# RCJ_OnStage2024_FC_mcu.net
KiCad netlist of a schematic drawn in Altium Designer
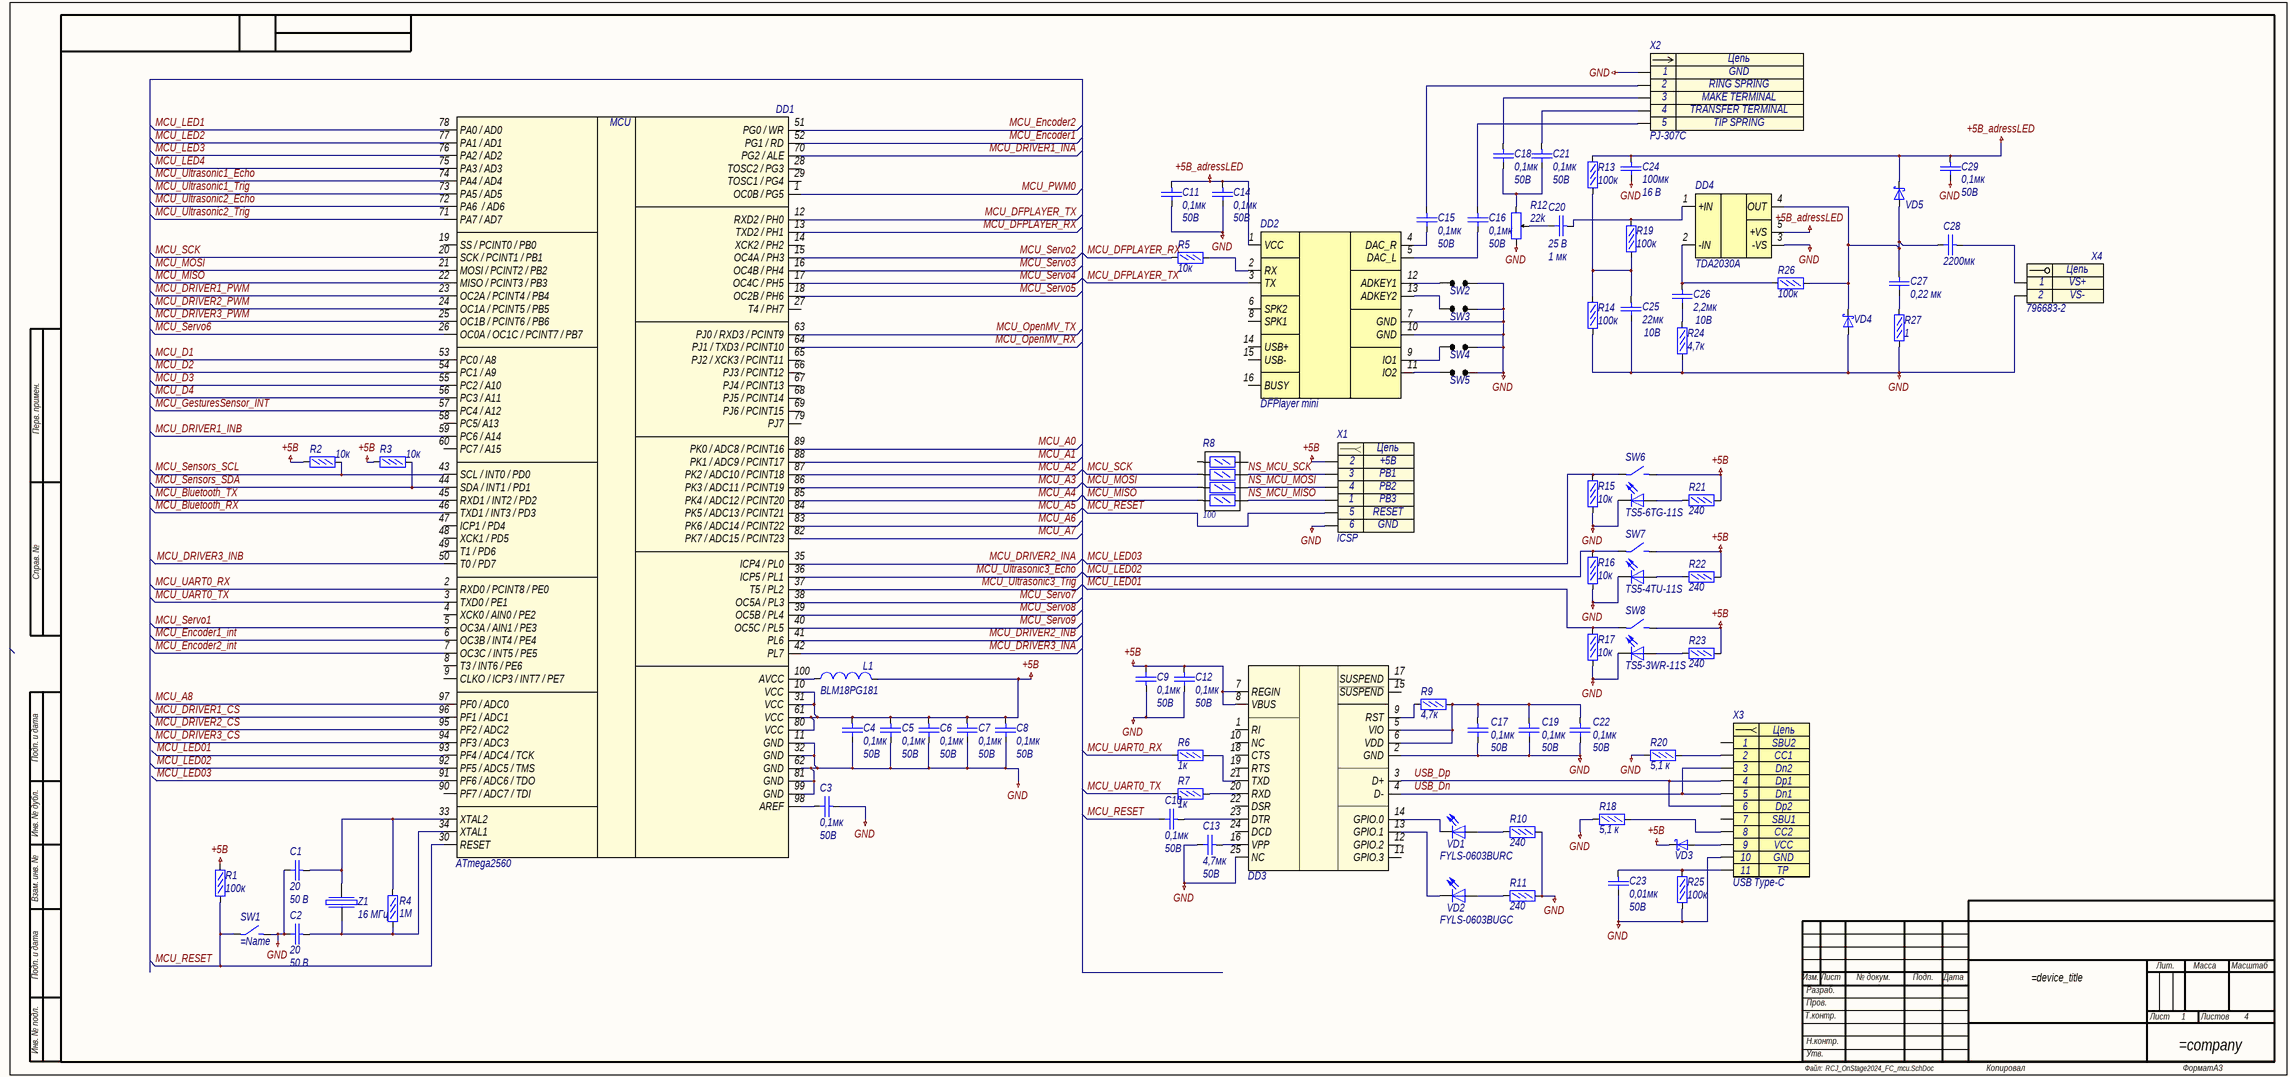
[diagram p0: RCJ_OnStage2024_FC_mcu.SchDoc]

(export (version "E")
  (design (tool "Eeschema 10.0.6"))
  (components
    (comp (ref "C1")
      (value "20")
      (footprint "C0603")
      (description "Конденсатор керамический 20пФ 50В")
      (fields (field (name "VOLTAGE") "50 В"))
      (libsource (lib "capacitors") (part "CC0603JRNPO9BN200"))
    )
    (comp (ref "C2")
      (value "20")
      (footprint "C0603")
      (description "Конденсатор керамический 20пФ 50В")
      (fields (field (name "VOLTAGE") "50 В"))
      (libsource (lib "capacitors") (part "CC0603JRNPO9BN200"))
    )
    (comp (ref "C3")
      (value "0,1мк")
      (footprint "C0603")
      (description "Конденсатор кер. 0,1мкФ 50В X7R")
      (fields (field (name "MANUFACTURER") "Murata") (field (name "VOLTAGE") "50В"))
      (libsource (lib "capacitors") (part "GRM188R71H104KA93D"))
    )
    (comp (ref "C4")
      (value "0,1мк")
      (footprint "C0603")
      (description "Конденсатор кер. 0,1мкФ 50В X7R")
      (fields (field (name "MANUFACTURER") "Murata") (field (name "VOLTAGE") "50В"))
      (libsource (lib "capacitors") (part "GRM188R71H104KA93D"))
    )
    (comp (ref "C5")
      (value "0,1мк")
      (footprint "C0603")
      (description "Конденсатор кер. 0,1мкФ 50В X7R")
      (fields (field (name "MANUFACTURER") "Murata") (field (name "VOLTAGE") "50В"))
      (libsource (lib "capacitors") (part "GRM188R71H104KA93D"))
    )
    (comp (ref "C6")
      (value "0,1мк")
      (footprint "C0603")
      (description "Конденсатор кер. 0,1мкФ 50В X7R")
      (fields (field (name "MANUFACTURER") "Murata") (field (name "VOLTAGE") "50В"))
      (libsource (lib "capacitors") (part "GRM188R71H104KA93D"))
    )
    (comp (ref "C7")
      (value "0,1мк")
      (footprint "C0603")
      (description "Конденсатор кер. 0,1мкФ 50В X7R")
      (fields (field (name "MANUFACTURER") "Murata") (field (name "VOLTAGE") "50В"))
      (libsource (lib "capacitors") (part "GRM188R71H104KA93D"))
    )
    (comp (ref "C8")
      (value "0,1мк")
      (footprint "C0603")
      (description "Конденсатор кер. 0,1мкФ 50В X7R")
      (fields (field (name "MANUFACTURER") "Murata") (field (name "VOLTAGE") "50В"))
      (libsource (lib "capacitors") (part "GRM188R71H104KA93D"))
    )
    (comp (ref "C9")
      (value "0,1мк")
      (footprint "C0603")
      (description "Конденсатор кер. 0,1мкФ 50В X7R")
      (fields (field (name "MANUFACTURER") "Murata") (field (name "VOLTAGE") "50В"))
      (libsource (lib "capacitors") (part "GRM188R71H104KA93D"))
    )
    (comp (ref "C10")
      (value "0,1мк")
      (footprint "C0603")
      (description "Конденсатор кер. 0,1мкФ 50В X7R")
      (fields (field (name "MANUFACTURER") "Murata") (field (name "VOLTAGE") "50В"))
      (libsource (lib "capacitors") (part "GRM188R71H104KA93D"))
    )
    (comp (ref "C11")
      (value "0,1мк")
      (footprint "C0603")
      (description "Конденсатор кер. 0,1мкФ 50В X7R")
      (fields (field (name "MANUFACTURER") "Murata") (field (name "VOLTAGE") "50В"))
      (libsource (lib "capacitors") (part "GRM188R71H104KA93D"))
    )
    (comp (ref "C12")
      (value "0,1мк")
      (footprint "C0603")
      (description "Конденсатор кер. 0,1мкФ 50В X7R")
      (fields (field (name "MANUFACTURER") "Murata") (field (name "VOLTAGE") "50В"))
      (libsource (lib "capacitors") (part "GRM188R71H104KA93D"))
    )
    (comp (ref "C13")
      (value "4,7мк")
      (footprint "C1210")
      (description "Конденсатор кер. 4,7мкФ 50В X7R")
      (fields (field (name "MANUFACTURER") "Murata") (field (name "VOLTAGE") "50В"))
      (libsource (lib "capacitors") (part "GRM32ER71H475KA88L"))
    )
    (comp (ref "C14")
      (value "0,1мк")
      (footprint "C0603")
      (description "Конденсатор кер. 0,1мкФ 50В X7R")
      (fields (field (name "MANUFACTURER") "Murata") (field (name "VOLTAGE") "50В"))
      (libsource (lib "capacitors") (part "GRM188R71H104KA93D"))
    )
    (comp (ref "C15")
      (value "0,1мк")
      (footprint "C0603")
      (description "Конденсатор кер. 0,1мкФ 50В X7R")
      (fields (field (name "MANUFACTURER") "Murata") (field (name "VOLTAGE") "50В"))
      (libsource (lib "capacitors") (part "GRM188R71H104KA93D"))
    )
    (comp (ref "C16")
      (value "0,1мк")
      (footprint "C0603")
      (description "Конденсатор кер. 0,1мкФ 50В X7R")
      (fields (field (name "MANUFACTURER") "Murata") (field (name "VOLTAGE") "50В"))
      (libsource (lib "capacitors") (part "GRM188R71H104KA93D"))
    )
    (comp (ref "C17")
      (value "0,1мк")
      (footprint "C0603")
      (description "Конденсатор кер. 0,1мкФ 50В X7R")
      (fields (field (name "MANUFACTURER") "Murata") (field (name "VOLTAGE") "50В"))
      (libsource (lib "capacitors") (part "GRM188R71H104KA93D"))
    )
    (comp (ref "C18")
      (value "0,1мк")
      (footprint "C0603")
      (description "Конденсатор кер. 0,1мкФ 50В X7R")
      (fields (field (name "MANUFACTURER") "Murata") (field (name "VOLTAGE") "50В"))
      (libsource (lib "capacitors") (part "GRM188R71H104KA93D"))
    )
    (comp (ref "C19")
      (value "0,1мк")
      (footprint "C0603")
      (description "Конденсатор кер. 0,1мкФ 50В X7R")
      (fields (field (name "MANUFACTURER") "Murata") (field (name "VOLTAGE") "50В"))
      (libsource (lib "capacitors") (part "GRM188R71H104KA93D"))
    )
    (comp (ref "C20")
      (value "1 мк")
      (footprint "C0805")
      (description "Конденсатор кер. 1мкФ 25В")
      (libsource (lib "capacitors") (part "CC0805KKX7R8BB105"))
    )
    (comp (ref "C21")
      (value "0,1мк")
      (footprint "C0603")
      (description "Конденсатор кер. 0,1мкФ 50В X7R")
      (fields (field (name "MANUFACTURER") "Murata") (field (name "VOLTAGE") "50В"))
      (libsource (lib "capacitors") (part "GRM188R71H104KA93D"))
    )
    (comp (ref "C22")
      (value "0,1мк")
      (footprint "C0603")
      (description "Конденсатор кер. 0,1мкФ 50В X7R")
      (fields (field (name "MANUFACTURER") "Murata") (field (name "VOLTAGE") "50В"))
      (libsource (lib "capacitors") (part "GRM188R71H104KA93D"))
    )
    (comp (ref "C23")
      (value "0,01мк")
      (footprint "C0603")
      (description "Конденсатор кер. 0,01мкФ 50В X7R")
      (fields (field (name "MANUFACTURER") "Murata") (field (name "VOLTAGE") "50В"))
      (libsource (lib "capacitors") (part "GRM188R71H103K"))
    )
    (comp (ref "C24")
      (value "100мк")
      (footprint "C1210")
      (description "Конденсатор керамический 100мкФ 16В")
      (fields (field (name "VOLTAGE") "16 В"))
      (libsource (lib "capacitors") (part "CC1210MKX5R7BB107"))
    )
    (comp (ref "C25")
      (value "22мк")
      (footprint "C1210")
      (description "Конденсатор кер. 22мкФ 10В X5R")
      (fields (field (name "MANUFACTURER") "Murata") (field (name "VOLTAGE") "10В"))
      (libsource (lib "capacitors") (part "GRM32ER61A226K"))
    )
    (comp (ref "C26")
      (value "2,2мк")
      (footprint "C0603")
      (description "Конденсатор кер. 2,2мкФ 10В X5R")
      (fields (field (name "MANUFACTURER") "Murata") (field (name "VOLTAGE") "10В"))
      (libsource (lib "capacitors") (part "GRM188R61A225K"))
    )
    (comp (ref "C27")
      (value "0,22 мк")
      (footprint "C0805")
      (description "Конденсатор кер. 0,22мкФ 50В")
      (fields (field (name "VOLTAGE") "50В"))
      (libsource (lib "capacitors") (part "CC0805JKX7R9BB224"))
    )
    (comp (ref "C28")
      (value "2200мк")
      (footprint "C0603")
      (description "Конденсатор керамический 0603")
      (libsource (lib "capacitors") (part "C0603"))
    )
    (comp (ref "C29")
      (value "0,1мк")
      (footprint "C0603")
      (description "Конденсатор кер. 0,1мкФ 50В X7R")
      (fields (field (name "MANUFACTURER") "Murata") (field (name "VOLTAGE") "50В"))
      (libsource (lib "capacitors") (part "GRM188R71H104KA93D"))
    )
    (comp (ref "DD1")
      (value "ATmega2560")
      (footprint "LQFP100")
      (description "Микроконтроллер")
      (libsource (lib "mcu") (part "ATmega2560"))
    )
    (comp (ref "DD2")
      (value "DFPlayer mini")
      (footprint "MP3-TF-16P")
      (libsource (lib "mcu") (part "DFPlayer mini"))
    )
    (comp (ref "DD3")
      (value "CP2104")
      (footprint "QFN-24")
      (description "Преобразователь интерфейсов USB-UART")
      (libsource (lib "mcu") (part "CP2104"))
    )
    (comp (ref "DD4")
      (value "TDA2030A")
      (footprint "TO-220-5B")
      (description "Усилитель звука")
      (libsource (lib "amplifiers") (part "TDA2030A"))
    )
    (comp (ref "L1")
      (value "BLM18PG181")
      (footprint "L0603")
      (description "Ферритовая бусина")
      (fields (field (name "MANUFACTURER") "Murata"))
      (libsource (lib "filters") (part "BLM18PG181"))
    )
    (comp (ref "R1")
      (value "100к")
      (footprint "R0603")
      (description "Резистор 100кОм 0,063Вт 1%")
      (libsource (lib "") (part "RC0603FR-07100KL_1"))
    )
    (comp (ref "R2")
      (value "10к")
      (footprint "R0603")
      (description "Резистор 10кОм 0,063Вт 1%")
      (fields (field (name "MANUFACTURER") "YAGEO") (field (name "TOLERANCE") "1%"))
      (libsource (lib "resistors") (part "RC0603FR-0710KL"))
    )
    (comp (ref "R3")
      (value "10к")
      (footprint "R0603")
      (description "Резистор 10кОм 0,063Вт 1%")
      (fields (field (name "MANUFACTURER") "YAGEO") (field (name "TOLERANCE") "1%"))
      (libsource (lib "resistors") (part "RC0603FR-0710KL"))
    )
    (comp (ref "R4")
      (value "1М")
      (footprint "R0603")
      (description "Резистор 1 МОм 0,063Вт 1%")
      (libsource (lib "resistors") (part "RC0603FR-071ML"))
    )
    (comp (ref "R5")
      (value "10к")
      (footprint "R0603")
      (description "Резистор 10кОм 0,063Вт 1%")
      (fields (field (name "MANUFACTURER") "YAGEO") (field (name "TOLERANCE") "1%"))
      (libsource (lib "resistors") (part "RC0603FR-0710KL"))
    )
    (comp (ref "R6")
      (value "1к")
      (footprint "R0603")
      (description "Резистор 1кОм 0,063Вт 1%")
      (fields (field (name "MANUFACTURER") "YAGEO") (field (name "TOLERANCE") "1%"))
      (libsource (lib "resistors") (part "RC0603FR-071KL"))
    )
    (comp (ref "R7")
      (value "1к")
      (footprint "R0603")
      (description "Резистор 1кОм 0,063Вт 1%")
      (fields (field (name "MANUFACTURER") "YAGEO") (field (name "TOLERANCE") "1%"))
      (libsource (lib "resistors") (part "RC0603FR-071KL"))
    )
    (comp (ref "R8")
      (value "100")
      (footprint "R0603x4")
      (description "Резисторы  0,125Вт")
      (libsource (lib "resistors") (part "Резисторная сборка х4 0,125"))
    )
    (comp (ref "R9")
      (value "4,7к")
      (footprint "R0603")
      (description "Резистор 4,7кОм 0,063Вт 1%")
      (fields (field (name "MANUFACTURER") "YAGEO") (field (name "TOLERANCE") "1%"))
      (libsource (lib "resistors") (part "RC0603FR-074K7L"))
    )
    (comp (ref "R10")
      (value "240")
      (footprint "R0603")
      (description "Резистор 240Ом 0,063Вт 1%")
      (fields (field (name "MANUFACTURER") "YAGEO") (field (name "TOLERANCE") "1%"))
      (libsource (lib "resistors") (part "RC0603FR-07240RL"))
    )
    (comp (ref "R11")
      (value "240")
      (footprint "R0603")
      (description "Резистор 240Ом 0,063Вт 1%")
      (fields (field (name "MANUFACTURER") "YAGEO") (field (name "TOLERANCE") "1%"))
      (libsource (lib "resistors") (part "RC0603FR-07240RL"))
    )
    (comp (ref "R12")
      (value "22k")
      (footprint "RM065")
      (description "Резистор переменный, 0.125 Вт, 20 кОм, 3-20, 20%")
      (libsource (lib "resistors") (part "RM065"))
    )
    (comp (ref "R13")
      (value "100к")
      (footprint "R0603")
      (description "Резистор 100кОм 0,063Вт 1%")
      (libsource (lib "") (part "RC0603FR-07100KL_1"))
    )
    (comp (ref "R14")
      (value "100к")
      (footprint "R0603")
      (description "Резистор 100кОм 0,063Вт 1%")
      (libsource (lib "") (part "RC0603FR-07100KL_1"))
    )
    (comp (ref "R15")
      (value "10к")
      (footprint "R0603")
      (description "Резистор 10кОм 0,063Вт 1%")
      (fields (field (name "MANUFACTURER") "YAGEO") (field (name "TOLERANCE") "1%"))
      (libsource (lib "") (part "RC0603FR-0710KL_1"))
    )
    (comp (ref "R16")
      (value "10к")
      (footprint "R0603")
      (description "Резистор 10кОм 0,063Вт 1%")
      (fields (field (name "MANUFACTURER") "YAGEO") (field (name "TOLERANCE") "1%"))
      (libsource (lib "") (part "RC0603FR-0710KL_1"))
    )
    (comp (ref "R17")
      (value "10к")
      (footprint "R0603")
      (description "Резистор 10кОм 0,063Вт 1%")
      (fields (field (name "MANUFACTURER") "YAGEO") (field (name "TOLERANCE") "1%"))
      (libsource (lib "") (part "RC0603FR-0710KL_1"))
    )
    (comp (ref "R18")
      (value "5,1 к")
      (footprint "R0603")
      (description "Резистор 5,1 кОм")
      (libsource (lib "resistors") (part "RC0603JR-075K1L"))
    )
    (comp (ref "R19")
      (value "100к")
      (footprint "R0603")
      (description "Резистор 100кОм 0,063Вт 1%")
      (libsource (lib "") (part "RC0603FR-07100KL_1"))
    )
    (comp (ref "R20")
      (value "5,1 к")
      (footprint "R0603")
      (description "Резистор 5,1 кОм")
      (libsource (lib "resistors") (part "RC0603JR-075K1L"))
    )
    (comp (ref "R21")
      (value "240")
      (footprint "R0603")
      (description "Резистор 240Ом 0,063Вт 1%")
      (fields (field (name "MANUFACTURER") "YAGEO") (field (name "TOLERANCE") "1%"))
      (libsource (lib "resistors") (part "RC0603FR-07240RL"))
    )
    (comp (ref "R22")
      (value "240")
      (footprint "R0603")
      (description "Резистор 240Ом 0,063Вт 1%")
      (fields (field (name "MANUFACTURER") "YAGEO") (field (name "TOLERANCE") "1%"))
      (libsource (lib "resistors") (part "RC0603FR-07240RL"))
    )
    (comp (ref "R23")
      (value "240")
      (footprint "R0603")
      (description "Резистор 240Ом 0,063Вт 1%")
      (fields (field (name "MANUFACTURER") "YAGEO") (field (name "TOLERANCE") "1%"))
      (libsource (lib "resistors") (part "RC0603FR-07240RL"))
    )
    (comp (ref "R24")
      (value "4,7к")
      (footprint "R0603")
      (description "Резистор 4,7кОм 0,063Вт 1%")
      (fields (field (name "MANUFACTURER") "YAGEO") (field (name "TOLERANCE") "1%"))
      (libsource (lib "") (part "RC0603FR-074K7L_1"))
    )
    (comp (ref "R25")
      (value "100к")
      (footprint "R0603")
      (description "Резистор 100кОм 0,063Вт 1%")
      (libsource (lib "") (part "RC0603FR-07100KL_1"))
    )
    (comp (ref "R26")
      (value "100к")
      (footprint "R0603")
      (description "Резистор 100кОм 0,063Вт 1%")
      (libsource (lib "resistors") (part "RC0603FR-07100KL"))
    )
    (comp (ref "R27")
      (value "1")
      (footprint "R0603")
      (description "Резистор 1Ом 0,063Вт 1%")
      (fields (field (name "MANUFACTURER") "YAGEO") (field (name "TOLERANCE") "1%"))
      (libsource (lib "resistors") (part "RC0603FR-071RL"))
    )
    (comp (ref "SW1") (value "~") (footprint "it-1187") (libsource (lib "connectors") (part "button")))
    (comp (ref "SW2")
      (value "~")
      (footprint "jumper")
      (description "Запаиваемая перемычка")
      (libsource (lib "connectors") (part "Jumper"))
    )
    (comp (ref "SW3")
      (value "~")
      (footprint "jumper")
      (description "Запаиваемая перемычка")
      (libsource (lib "connectors") (part "Jumper"))
    )
    (comp (ref "SW4")
      (value "~")
      (footprint "jumper")
      (description "Запаиваемая перемычка")
      (libsource (lib "connectors") (part "Jumper"))
    )
    (comp (ref "SW5")
      (value "~")
      (footprint "jumper")
      (description "Запаиваемая перемычка")
      (libsource (lib "connectors") (part "Jumper"))
    )
    (comp (ref "SW6")
      (value "TS5-6TG-11S")
      (footprint "TS5")
      (description "Миниатюрная кнопка с LED-подсветкой (зеленая)")
      (libsource (lib "connectors") (part "TS5-6TG-11S"))
    )
    (comp (ref "SW7")
      (value "TS5-4TU-11S")
      (footprint "TS5")
      (description "Миниатюрная кнопка с LED-подсветкой (синяя)")
      (libsource (lib "connectors") (part "TS5-4TU-11S"))
    )
    (comp (ref "SW8")
      (value "TS5-3WR-11S")
      (footprint "TS5")
      (description "Миниатюрная кнопка с LED-подсветкой (красная)")
      (libsource (lib "connectors") (part "TS5-3WR-11S"))
    )
    (comp (ref "VD1")
      (value "FYLS-0603BURC")
      (footprint "LED0603_RED")
      (description "Светодиод")
      (fields (field (name "NAME") "FYLS-0603BURC"))
      (libsource (lib "diodes") (part "LED"))
    )
    (comp (ref "VD2")
      (value "FYLS-0603BUGC")
      (footprint "LED0603_GREEN")
      (description "Светодиод")
      (fields (field (name "NAME") "FYLS-0603BUGC"))
      (libsource (lib "diodes") (part "LED"))
    )
    (comp (ref "VD3")
      (value "MBR140SFT1G")
      (footprint "SOD123")
      (description "Диод Шоттки 40В 1А")
      (libsource (lib "diodes") (part "MBR140SFT1G"))
    )
    (comp (ref "VD4")
      (value "MBR140SFT1G")
      (footprint "SOD123")
      (description "Диод Шоттки 40В 1А")
      (libsource (lib "diodes") (part "MBR140SFT1G"))
    )
    (comp (ref "VD5")
      (value "MBR140SFT1G")
      (footprint "SOD123")
      (description "Диод Шоттки 40В 1А")
      (libsource (lib "diodes") (part "MBR140SFT1G"))
    )
    (comp (ref "X1")
      (value "ICSP")
      (footprint "PLS-3x2")
      (description "Разъем для программатора")
      (libsource (lib "connectors") (part "ICSP"))
    )
    (comp (ref "X2")
      (value "PJ-307C")
      (footprint "PJ-307C")
      (description "Φ3.5mm, 3 poles, Audio Jack")
      (libsource (lib "connectors") (part "PJ-307C"))
    )
    (comp (ref "X3")
      (value "USB Type-C")
      (footprint "USB4105-15-A-120")
      (description "USB Type-C USB4105-GF-A / GCT")
      (libsource (lib "connectors") (part "USB4105"))
    )
    (comp (ref "X4")
      (value "796683-2")
      (footprint "796683-2")
      (description "Винтовой клеммник (наборный 2х2)")
      (libsource (lib "connectors") (part "796683-2"))
    )
    (comp (ref "Z1")
      (value "16 MГц")
      (footprint "QSMD3.2x2.5")
      (description "Кварцевый резонатор")
      (libsource (lib "filters") (part "QuartzCystal"))
    )
  )
  (nets
    (net (code "1") (name "+5В") (class "Default")
      (node (ref "C12") (pin "2") (pinfunction "2_2") (pintype "passive"))
      (node (ref "C4") (pin "2") (pinfunction "2_2") (pintype "passive"))
      (node (ref "C5") (pin "2") (pinfunction "2_2") (pintype "passive"))
      (node (ref "C6") (pin "2") (pinfunction "2_2") (pintype "passive"))
      (node (ref "C7") (pin "2") (pinfunction "2_2") (pintype "passive"))
      (node (ref "C8") (pin "2") (pinfunction "2_2") (pintype "passive"))
      (node (ref "C9") (pin "1") (pinfunction "1_1") (pintype "passive"))
      (node (ref "DD1") (pin "10") (pinfunction "VCC_10") (pintype "passive"))
      (node (ref "DD1") (pin "31") (pinfunction "VCC_31") (pintype "passive"))
      (node (ref "DD1") (pin "61") (pinfunction "VCC_61") (pintype "passive"))
      (node (ref "DD1") (pin "80") (pinfunction "VCC_80") (pintype "passive"))
      (node (ref "DD3") (pin "7") (pinfunction "REGIN_7") (pintype "passive"))
      (node (ref "DD3") (pin "8") (pinfunction "VBUS_8") (pintype "passive"))
      (node (ref "L1") (pin "2") (pinfunction "4_2") (pintype "passive"))
      (node (ref "R1") (pin "2") (pinfunction "2_2") (pintype "passive"))
      (node (ref "R2") (pin "1") (pinfunction "1_1") (pintype "passive"))
      (node (ref "R21") (pin "2") (pinfunction "2_2") (pintype "passive"))
      (node (ref "R22") (pin "2") (pinfunction "2_2") (pintype "passive"))
      (node (ref "R23") (pin "2") (pinfunction "2_2") (pintype "passive"))
      (node (ref "R3") (pin "1") (pinfunction "1_1") (pintype "passive"))
      (node (ref "SW6") (pin "4") (pinfunction "4_4") (pintype "passive"))
      (node (ref "SW7") (pin "4") (pinfunction "4_4") (pintype "passive"))
      (node (ref "SW8") (pin "4") (pinfunction "4_4") (pintype "passive"))
      (node (ref "VD3") (pin "1") (pinfunction "K_1") (pintype "passive"))
      (node (ref "X1") (pin "2") (pinfunction "2_2") (pintype "passive"))
    )
    (net (code "2") (name "+5В_adressLED") (class "Default")
      (node (ref "C11") (pin "2") (pinfunction "2_2") (pintype "passive"))
      (node (ref "C14") (pin "2") (pinfunction "2_2") (pintype "passive"))
      (node (ref "C24") (pin "2") (pinfunction "2_2") (pintype "passive"))
      (node (ref "C29") (pin "2") (pinfunction "2_2") (pintype "passive"))
      (node (ref "DD2") (pin "1") (pinfunction "VCC_1") (pintype "passive"))
      (node (ref "DD4") (pin "5") (pinfunction "+VS_5") (pintype "passive"))
      (node (ref "R13") (pin "2") (pinfunction "2_2") (pintype "passive"))
      (node (ref "VD5") (pin "1") (pinfunction "K_1") (pintype "passive"))
    )
    (net (code "3") (name "/MCU_A0") (class "Default")
      (node (ref "DD1") (pin "89") (pinfunction "PK0_/_ADC8_/_PCINT16_89") (pintype "passive"))
    )
    (net (code "4") (name "/MCU_A1") (class "Default")
      (node (ref "DD1") (pin "88") (pinfunction "PK1_/_ADC9_/_PCINT17_88") (pintype "passive"))
    )
    (net (code "5") (name "/MCU_A2") (class "Default")
      (node (ref "DD1") (pin "87") (pinfunction "PK2_/_ADC10_/_PCINT18_87") (pintype "passive"))
    )
    (net (code "6") (name "/MCU_A3") (class "Default")
      (node (ref "DD1") (pin "86") (pinfunction "PK3_/_ADC11_/_PCINT19_86") (pintype "passive"))
    )
    (net (code "7") (name "/MCU_A4") (class "Default")
      (node (ref "DD1") (pin "85") (pinfunction "PK4_/_ADC12_/_PCINT20_85") (pintype "passive"))
    )
    (net (code "8") (name "/MCU_A5") (class "Default")
      (node (ref "DD1") (pin "84") (pinfunction "PK5_/_ADC13_/_PCINT21_84") (pintype "passive"))
    )
    (net (code "9") (name "/MCU_A6") (class "Default")
      (node (ref "DD1") (pin "83") (pinfunction "PK6_/_ADC14_/_PCINT22_83") (pintype "passive"))
    )
    (net (code "10") (name "/MCU_A7") (class "Default")
      (node (ref "DD1") (pin "82") (pinfunction "PK7_/_ADC15_/_PCINT23_82") (pintype "passive"))
    )
    (net (code "11") (name "/MCU_A8") (class "Default")
      (node (ref "DD1") (pin "97") (pinfunction "PF0_/_ADC0_97") (pintype "passive"))
    )
    (net (code "12") (name "/MCU_Bluetooth_RX") (class "Default")
      (node (ref "DD1") (pin "46") (pinfunction "TXD1_/_INT3_/_PD3_46") (pintype "passive"))
    )
    (net (code "13") (name "/MCU_Bluetooth_TX") (class "Default")
      (node (ref "DD1") (pin "45") (pinfunction "RXD1_/_INT2_/_PD2_45") (pintype "passive"))
    )
    (net (code "14") (name "/MCU_D1") (class "Default")
      (node (ref "DD1") (pin "53") (pinfunction "PC0_/_A8_53") (pintype "passive"))
    )
    (net (code "15") (name "/MCU_D2") (class "Default")
      (node (ref "DD1") (pin "54") (pinfunction "PC1_/_A9_54") (pintype "passive"))
    )
    (net (code "16") (name "/MCU_D3") (class "Default")
      (node (ref "DD1") (pin "55") (pinfunction "PC2_/_A10_55") (pintype "passive"))
    )
    (net (code "17") (name "/MCU_D4") (class "Default")
      (node (ref "DD1") (pin "56") (pinfunction "PC3_/_A11_56") (pintype "passive"))
    )
    (net (code "18") (name "/MCU_DFPLAYER_RX") (class "Default")
      (node (ref "DD1") (pin "13") (pinfunction "TXD2_/_PH1_13") (pintype "passive"))
      (node (ref "R5") (pin "1") (pinfunction "1_1") (pintype "passive"))
    )
    (net (code "19") (name "/MCU_DFPLAYER_TX") (class "Default")
      (node (ref "DD1") (pin "12") (pinfunction "RXD2_/_PH0_12") (pintype "passive"))
      (node (ref "DD2") (pin "3") (pinfunction "TX_3") (pintype "passive"))
    )
    (net (code "20") (name "/MCU_DRIVER1_CS") (class "Default")
      (node (ref "DD1") (pin "96") (pinfunction "PF1_/_ADC1_96") (pintype "passive"))
    )
    (net (code "21") (name "/MCU_DRIVER1_INA") (class "Default")
      (node (ref "DD1") (pin "70") (pinfunction "PG2_/_ALE_70") (pintype "passive"))
    )
    (net (code "22") (name "/MCU_DRIVER1_INB") (class "Default")
      (node (ref "DD1") (pin "59") (pinfunction "PC6_/_A14_59") (pintype "passive"))
    )
    (net (code "23") (name "/MCU_DRIVER1_PWM") (class "Default")
      (node (ref "DD1") (pin "23") (pinfunction "OC2A_/_PCINT4_/_PB4_23") (pintype "passive"))
    )
    (net (code "24") (name "/MCU_DRIVER2_CS") (class "Default")
      (node (ref "DD1") (pin "95") (pinfunction "PF2_/_ADC2_95") (pintype "passive"))
    )
    (net (code "25") (name "/MCU_DRIVER2_INA") (class "Default")
      (node (ref "DD1") (pin "35") (pinfunction "ICP4_/_PL0_35") (pintype "passive"))
    )
    (net (code "26") (name "/MCU_DRIVER2_INB") (class "Default")
      (node (ref "DD1") (pin "41") (pinfunction "PL6_41") (pintype "passive"))
    )
    (net (code "27") (name "/MCU_DRIVER2_PWM") (class "Default")
      (node (ref "DD1") (pin "24") (pinfunction "OC1A_/_PCINT5_/_PB5_24") (pintype "passive"))
    )
    (net (code "28") (name "/MCU_DRIVER3_CS") (class "Default")
      (node (ref "DD1") (pin "94") (pinfunction "PF3_/_ADC3_94") (pintype "passive"))
    )
    (net (code "29") (name "/MCU_DRIVER3_INA") (class "Default")
      (node (ref "DD1") (pin "42") (pinfunction "PL7_42") (pintype "passive"))
    )
    (net (code "30") (name "/MCU_DRIVER3_INB") (class "Default")
      (node (ref "DD1") (pin "50") (pinfunction "T0_/_PD7_50") (pintype "passive"))
    )
    (net (code "31") (name "/MCU_DRIVER3_PWM") (class "Default")
      (node (ref "DD1") (pin "25") (pinfunction "OC1B_/_PCINT6_/_PB6_25") (pintype "passive"))
    )
    (net (code "32") (name "/MCU_Encoder1") (class "Default")
      (node (ref "DD1") (pin "52") (pinfunction "PG1_/_RD_52") (pintype "passive"))
    )
    (net (code "33") (name "/MCU_Encoder1_int") (class "Default")
      (node (ref "DD1") (pin "6") (pinfunction "OC3B_/_INT4_/_PE4_6") (pintype "passive"))
    )
    (net (code "34") (name "/MCU_Encoder2") (class "Default")
      (node (ref "DD1") (pin "51") (pinfunction "PG0_/_WR_51") (pintype "passive"))
    )
    (net (code "35") (name "/MCU_Encoder2_int") (class "Default")
      (node (ref "DD1") (pin "7") (pinfunction "OC3C_/_INT5_/_PE5_7") (pintype "passive"))
    )
    (net (code "36") (name "/MCU_GesturesSensor_INT") (class "Default")
      (node (ref "DD1") (pin "57") (pinfunction "PC4_/_A12_57") (pintype "passive"))
    )
    (net (code "37") (name "/MCU_LED1") (class "Default")
      (node (ref "DD1") (pin "78") (pinfunction "PA0_/_AD0_78") (pintype "passive"))
    )
    (net (code "38") (name "/MCU_LED01") (class "Default")
      (node (ref "DD1") (pin "93") (pinfunction "PF4_/_ADC4_/_TCK_93") (pintype "passive"))
      (node (ref "R17") (pin "2") (pinfunction "2_2") (pintype "passive"))
      (node (ref "SW8") (pin "1") (pinfunction "1_1") (pintype "passive"))
    )
    (net (code "39") (name "/MCU_LED02") (class "Default")
      (node (ref "DD1") (pin "92") (pinfunction "PF5_/_ADC5_/_TMS_92") (pintype "passive"))
      (node (ref "R16") (pin "2") (pinfunction "2_2") (pintype "passive"))
      (node (ref "SW7") (pin "1") (pinfunction "1_1") (pintype "passive"))
    )
    (net (code "40") (name "/MCU_LED2") (class "Default")
      (node (ref "DD1") (pin "77") (pinfunction "PA1_/_AD1_77") (pintype "passive"))
    )
    (net (code "41") (name "/MCU_LED03") (class "Default")
      (node (ref "DD1") (pin "91") (pinfunction "PF6_/_ADC6_/_TDO_91") (pintype "passive"))
      (node (ref "R15") (pin "2") (pinfunction "2_2") (pintype "passive"))
      (node (ref "SW6") (pin "1") (pinfunction "1_1") (pintype "passive"))
    )
    (net (code "42") (name "/MCU_LED3") (class "Default")
      (node (ref "DD1") (pin "76") (pinfunction "PA2_/_AD2_76") (pintype "passive"))
    )
    (net (code "43") (name "/MCU_LED4") (class "Default")
      (node (ref "DD1") (pin "75") (pinfunction "PA3_/_AD3_75") (pintype "passive"))
    )
    (net (code "44") (name "/MCU_MISO") (class "Default")
      (node (ref "DD1") (pin "22") (pinfunction "MISO_/_PCINT3_/_PB3_22") (pintype "passive"))
      (node (ref "R8") (pin "3") (pinfunction "7_3") (pintype "passive"))
    )
    (net (code "45") (name "/MCU_MOSI") (class "Default")
      (node (ref "DD1") (pin "21") (pinfunction "MOSI_/_PCINT2_/_PB2_21") (pintype "passive"))
      (node (ref "R8") (pin "5") (pinfunction "5_5") (pintype "passive"))
    )
    (net (code "46") (name "/MCU_OpenMV_RX") (class "Default")
      (node (ref "DD1") (pin "64") (pinfunction "PJ1_/_TXD3_/_PCINT10_64") (pintype "passive"))
    )
    (net (code "47") (name "/MCU_OpenMV_TX") (class "Default")
      (node (ref "DD1") (pin "63") (pinfunction "PJ0_/_RXD3_/_PCINT9_63") (pintype "passive"))
    )
    (net (code "48") (name "/MCU_PWM0") (class "Default")
      (node (ref "DD1") (pin "1") (pinfunction "OC0B_/_PG5_1") (pintype "passive"))
    )
    (net (code "49") (name "/MCU_RESET") (class "Default")
      (node (ref "C10") (pin "1") (pinfunction "1_1") (pintype "passive"))
      (node (ref "DD1") (pin "30") (pinfunction "RESET_30") (pintype "passive"))
      (node (ref "R1") (pin "1") (pinfunction "1_1") (pintype "passive"))
      (node (ref "SW1") (pin "1") (pinfunction "1_1") (pintype "passive"))
      (node (ref "X1") (pin "5") (pinfunction "5_5") (pintype "passive"))
    )
    (net (code "50") (name "/MCU_SCK") (class "Default")
      (node (ref "DD1") (pin "20") (pinfunction "SCK_/_PCINT1_/_PB1_20") (pintype "passive"))
      (node (ref "R8") (pin "7") (pinfunction "3_7") (pintype "passive"))
    )
    (net (code "51") (name "/MCU_Sensors_SCL") (class "Default")
      (node (ref "DD1") (pin "43") (pinfunction "SCL_/_INT0_/_PD0_43") (pintype "passive"))
      (node (ref "R2") (pin "2") (pinfunction "2_2") (pintype "passive"))
    )
    (net (code "52") (name "/MCU_Sensors_SDA") (class "Default")
      (node (ref "DD1") (pin "44") (pinfunction "SDA_/_INT1_/_PD1_44") (pintype "passive"))
      (node (ref "R3") (pin "2") (pinfunction "2_2") (pintype "passive"))
    )
    (net (code "53") (name "/MCU_Servo1") (class "Default")
      (node (ref "DD1") (pin "5") (pinfunction "OC3A_/_AIN1_/_PE3_5") (pintype "passive"))
    )
    (net (code "54") (name "/MCU_Servo2") (class "Default")
      (node (ref "DD1") (pin "15") (pinfunction "OC4A_/_PH3_15") (pintype "passive"))
    )
    (net (code "55") (name "/MCU_Servo3") (class "Default")
      (node (ref "DD1") (pin "16") (pinfunction "OC4B_/_PH4_16") (pintype "passive"))
    )
    (net (code "56") (name "/MCU_Servo4") (class "Default")
      (node (ref "DD1") (pin "17") (pinfunction "OC4C_/_PH5_17") (pintype "passive"))
    )
    (net (code "57") (name "/MCU_Servo5") (class "Default")
      (node (ref "DD1") (pin "18") (pinfunction "OC2B_/_PH6_18") (pintype "passive"))
    )
    (net (code "58") (name "/MCU_Servo6") (class "Default")
      (node (ref "DD1") (pin "26") (pinfunction "OC0A_/_OC1C_/_PCINT7_/_PB7_26") (pintype "passive"))
    )
    (net (code "59") (name "/MCU_Servo7") (class "Default")
      (node (ref "DD1") (pin "38") (pinfunction "OC5A_/_PL3_38") (pintype "passive"))
    )
    (net (code "60") (name "/MCU_Servo8") (class "Default")
      (node (ref "DD1") (pin "39") (pinfunction "OC5B_/_PL4_39") (pintype "passive"))
    )
    (net (code "61") (name "/MCU_Servo9") (class "Default")
      (node (ref "DD1") (pin "40") (pinfunction "OC5C_/_PL5_40") (pintype "passive"))
    )
    (net (code "62") (name "/MCU_UART0_RX") (class "Default")
      (node (ref "DD1") (pin "2") (pinfunction "RXD0_/_PCINT8_/_PE0_2") (pintype "passive"))
      (node (ref "R6") (pin "1") (pinfunction "1_1") (pintype "passive"))
    )
    (net (code "63") (name "/MCU_UART0_TX") (class "Default")
      (node (ref "DD1") (pin "3") (pinfunction "TXD0_/_PE1_3") (pintype "passive"))
      (node (ref "R7") (pin "1") (pinfunction "1_1") (pintype "passive"))
    )
    (net (code "64") (name "/MCU_Ultrasonic1_Echo") (class "Default")
      (node (ref "DD1") (pin "74") (pinfunction "PA4_/_AD4_74") (pintype "passive"))
    )
    (net (code "65") (name "/MCU_Ultrasonic1_Trig") (class "Default")
      (node (ref "DD1") (pin "73") (pinfunction "PA5_/_AD5_73") (pintype "passive"))
    )
    (net (code "66") (name "/MCU_Ultrasonic2_Echo") (class "Default")
      (node (ref "DD1") (pin "72") (pinfunction "PA6__/_AD6_72") (pintype "passive"))
    )
    (net (code "67") (name "/MCU_Ultrasonic2_Trig") (class "Default")
      (node (ref "DD1") (pin "71") (pinfunction "PA7_/_AD7_71") (pintype "passive"))
    )
    (net (code "68") (name "/MCU_Ultrasonic3_Echo") (class "Default")
      (node (ref "DD1") (pin "36") (pinfunction "ICP5_/_PL1_36") (pintype "passive"))
    )
    (net (code "69") (name "/MCU_Ultrasonic3_Trig") (class "Default")
      (node (ref "DD1") (pin "37") (pinfunction "T5_/_PL2_37") (pintype "passive"))
    )
    (net (code "70") (name "/NS_MCU_MISO") (class "Default")
      (node (ref "R8") (pin "4") (pinfunction "8_4") (pintype "passive"))
      (node (ref "X1") (pin "1") (pinfunction "1_1") (pintype "passive"))
    )
    (net (code "71") (name "/NS_MCU_MOSI") (class "Default")
      (node (ref "R8") (pin "6") (pinfunction "6_6") (pintype "passive"))
      (node (ref "X1") (pin "4") (pinfunction "4_4") (pintype "passive"))
    )
    (net (code "72") (name "/NS_MCU_SCK") (class "Default")
      (node (ref "R8") (pin "8") (pinfunction "4_8") (pintype "passive"))
      (node (ref "X1") (pin "3") (pinfunction "3_3") (pintype "passive"))
    )
    (net (code "73") (name "/USB_Dn") (class "Default")
      (node (ref "DD3") (pin "4") (pinfunction "D-_4") (pintype "passive"))
      (node (ref "X3") (pin "3") (pinfunction "B7_3") (pintype "passive"))
      (node (ref "X3") (pin "5") (pinfunction "A7_5") (pintype "passive"))
    )
    (net (code "74") (name "/USB_Dp") (class "Default")
      (node (ref "DD3") (pin "3") (pinfunction "D+_3") (pintype "passive"))
      (node (ref "X3") (pin "4") (pinfunction "A6_4") (pintype "passive"))
      (node (ref "X3") (pin "6") (pinfunction "B6_6") (pintype "passive"))
    )
    (net (code "75") (name "GND") (class "Default")
      (node (ref "C1") (pin "1") (pinfunction "1_1") (pintype "passive"))
      (node (ref "C11") (pin "1") (pinfunction "1_1") (pintype "passive"))
      (node (ref "C12") (pin "1") (pinfunction "1_1") (pintype "passive"))
      (node (ref "C13") (pin "1") (pinfunction "1_1") (pintype "passive"))
      (node (ref "C14") (pin "1") (pinfunction "1_1") (pintype "passive"))
      (node (ref "C17") (pin "1") (pinfunction "1_1") (pintype "passive"))
      (node (ref "C19") (pin "1") (pinfunction "1_1") (pintype "passive"))
      (node (ref "C2") (pin "1") (pinfunction "1_1") (pintype "passive"))
      (node (ref "C22") (pin "1") (pinfunction "1_1") (pintype "passive"))
      (node (ref "C23") (pin "1") (pinfunction "1_1") (pintype "passive"))
      (node (ref "C24") (pin "1") (pinfunction "1_1") (pintype "passive"))
      (node (ref "C25") (pin "1") (pinfunction "1_1") (pintype "passive"))
      (node (ref "C29") (pin "1") (pinfunction "1_1") (pintype "passive"))
      (node (ref "C3") (pin "2") (pinfunction "2_2") (pintype "passive"))
      (node (ref "C4") (pin "1") (pinfunction "1_1") (pintype "passive"))
      (node (ref "C5") (pin "1") (pinfunction "1_1") (pintype "passive"))
      (node (ref "C6") (pin "1") (pinfunction "1_1") (pintype "passive"))
      (node (ref "C7") (pin "1") (pinfunction "1_1") (pintype "passive"))
      (node (ref "C8") (pin "1") (pinfunction "1_1") (pintype "passive"))
      (node (ref "C9") (pin "2") (pinfunction "2_2") (pintype "passive"))
      (node (ref "DD1") (pin "11") (pinfunction "GND_11") (pintype "passive"))
      (node (ref "DD1") (pin "32") (pinfunction "GND_32") (pintype "passive"))
      (node (ref "DD1") (pin "62") (pinfunction "GND_62") (pintype "passive"))
      (node (ref "DD1") (pin "81") (pinfunction "GND_81") (pintype "passive"))
      (node (ref "DD1") (pin "99") (pinfunction "GND_99") (pintype "passive"))
      (node (ref "DD2") (pin "10") (pinfunction "GND_10") (pintype "passive"))
      (node (ref "DD2") (pin "7") (pinfunction "GND_7") (pintype "passive"))
      (node (ref "DD3") (pin "2") (pinfunction "GND_2") (pintype "passive"))
      (node (ref "DD3") (pin "25") (pinfunction "NC_25") (pintype "passive"))
      (node (ref "DD4") (pin "3") (pinfunction "-VS_3") (pintype "passive"))
      (node (ref "R10") (pin "2") (pinfunction "2_2") (pintype "passive"))
      (node (ref "R11") (pin "2") (pinfunction "2_2") (pintype "passive"))
      (node (ref "R12") (pin "2") (pinfunction "2_2") (pintype "passive"))
      (node (ref "R14") (pin "1") (pinfunction "1_1") (pintype "passive"))
      (node (ref "R15") (pin "1") (pinfunction "1_1") (pintype "passive"))
      (node (ref "R16") (pin "1") (pinfunction "1_1") (pintype "passive"))
      (node (ref "R17") (pin "1") (pinfunction "1_1") (pintype "passive"))
      (node (ref "R18") (pin "1") (pinfunction "1_1") (pintype "passive"))
      (node (ref "R20") (pin "1") (pinfunction "1_1") (pintype "passive"))
      (node (ref "R24") (pin "1") (pinfunction "1_1") (pintype "passive"))
      (node (ref "R25") (pin "1") (pinfunction "1_1") (pintype "passive"))
      (node (ref "R27") (pin "1") (pinfunction "1_1") (pintype "passive"))
      (node (ref "SW1") (pin "2") (pinfunction "2_2") (pintype "passive"))
      (node (ref "SW2") (pin "2") (pinfunction "2_2") (pintype "passive"))
      (node (ref "SW3") (pin "2") (pinfunction "2_2") (pintype "passive"))
      (node (ref "SW4") (pin "2") (pinfunction "2_2") (pintype "passive"))
      (node (ref "SW5") (pin "2") (pinfunction "2_2") (pintype "passive"))
      (node (ref "SW6") (pin "5") (pinfunction "5_5") (pintype "passive"))
      (node (ref "SW7") (pin "5") (pinfunction "5_5") (pintype "passive"))
      (node (ref "SW8") (pin "5") (pinfunction "5_5") (pintype "passive"))
      (node (ref "VD4") (pin "2") (pinfunction "A_2") (pintype "passive"))
      (node (ref "X1") (pin "6") (pinfunction "6_6") (pintype "passive"))
      (node (ref "X2") (pin "1") (pinfunction "1_1") (pintype "passive"))
      (node (ref "X3") (pin "10") (pinfunction "VCC_10") (pintype "passive"))
      (node (ref "X4") (pin "2") (pinfunction "2_2") (pintype "passive"))
    )
    (net (code "76") (name "Net-(C15-Pad2)") (class "Default")
      (node (ref "C15") (pin "2") (pinfunction "2_2") (pintype "passive"))
      (node (ref "X2") (pin "2") (pinfunction "2_2") (pintype "passive"))
    )
    (net (code "77") (name "Net-(C16-Pad2)") (class "Default")
      (node (ref "C16") (pin "2") (pinfunction "2_2") (pintype "passive"))
      (node (ref "X2") (pin "5") (pinfunction "5_5") (pintype "passive"))
    )
    (net (code "78") (name "Net-(C18-Pad1)") (class "Default")
      (node (ref "C18") (pin "1") (pinfunction "1_1") (pintype "passive"))
      (node (ref "C21") (pin "1") (pinfunction "1_1") (pintype "passive"))
      (node (ref "R12") (pin "1") (pinfunction "1_1") (pintype "passive"))
    )
    (net (code "79") (name "Net-(C18-Pad2)") (class "Default")
      (node (ref "C18") (pin "2") (pinfunction "2_2") (pintype "passive"))
      (node (ref "X2") (pin "3") (pinfunction "3_3") (pintype "passive"))
    )
    (net (code "80") (name "Net-(C20-Pad1)") (class "Default")
      (node (ref "C20") (pin "1") (pinfunction "1_1") (pintype "passive"))
      (node (ref "R12") (pin "3") (pinfunction "3_3") (pintype "passive"))
    )
    (net (code "81") (name "Net-(C21-Pad2)") (class "Default")
      (node (ref "C21") (pin "2") (pinfunction "2_2") (pintype "passive"))
      (node (ref "X2") (pin "4") (pinfunction "4_4") (pintype "passive"))
    )
    (net (code "82") (name "Net-(C23-Pad2)") (class "Default")
      (node (ref "C23") (pin "2") (pinfunction "2_2") (pintype "passive"))
      (node (ref "R25") (pin "2") (pinfunction "2_2") (pintype "passive"))
      (node (ref "X3") (pin "TP") (pinfunction "TP_TP") (pintype "passive"))
    )
    (net (code "83") (name "Net-(C25-Pad2)") (class "Default")
      (node (ref "C25") (pin "2") (pinfunction "2_2") (pintype "passive"))
      (node (ref "R13") (pin "1") (pinfunction "1_1") (pintype "passive"))
      (node (ref "R14") (pin "2") (pinfunction "2_2") (pintype "passive"))
      (node (ref "R19") (pin "1") (pinfunction "1_1") (pintype "passive"))
    )
    (net (code "84") (name "Net-(C26-Pad1)") (class "Default")
      (node (ref "C26") (pin "1") (pinfunction "1_1") (pintype "passive"))
      (node (ref "R24") (pin "2") (pinfunction "2_2") (pintype "passive"))
    )
    (net (code "85") (name "Net-(C27-Pad1)") (class "Default")
      (node (ref "C27") (pin "1") (pinfunction "1_1") (pintype "passive"))
      (node (ref "R27") (pin "2") (pinfunction "2_2") (pintype "passive"))
    )
    (net (code "86") (name "Net-(C28-Pad2)") (class "Default")
      (node (ref "C28") (pin "2") (pinfunction "2_2") (pintype "passive"))
      (node (ref "X4") (pin "1") (pinfunction "1_1") (pintype "passive"))
    )
    (net (code "87") (name "Net-(DD1-AREF)") (class "Default")
      (node (ref "C3") (pin "1") (pinfunction "1_1") (pintype "passive"))
      (node (ref "DD1") (pin "98") (pinfunction "AREF_98") (pintype "passive"))
    )
    (net (code "88") (name "Net-(DD1-AVCC)") (class "Default")
      (node (ref "DD1") (pin "100") (pinfunction "AVCC_100") (pintype "passive"))
      (node (ref "L1") (pin "1") (pinfunction "3_1") (pintype "passive"))
    )
    (net (code "89") (name "Net-(DD1-XTAL1)") (class "Default")
      (node (ref "C2") (pin "2") (pinfunction "2_2") (pintype "passive"))
      (node (ref "DD1") (pin "34") (pinfunction "XTAL1_34") (pintype "passive"))
      (node (ref "R4") (pin "1") (pinfunction "1_1") (pintype "passive"))
      (node (ref "Z1") (pin "1") (pintype "passive"))
    )
    (net (code "90") (name "Net-(DD1-XTAL2)") (class "Default")
      (node (ref "C1") (pin "2") (pinfunction "2_2") (pintype "passive"))
      (node (ref "DD1") (pin "33") (pinfunction "XTAL2_33") (pintype "passive"))
      (node (ref "R4") (pin "2") (pinfunction "2_2") (pintype "passive"))
      (node (ref "Z1") (pin "2") (pintype "passive"))
    )
    (net (code "91") (name "Net-(DD2-ADKEY1)") (class "Default")
      (node (ref "DD2") (pin "12") (pinfunction "ADKEY1_12") (pintype "passive"))
      (node (ref "SW2") (pin "1") (pinfunction "1_1") (pintype "passive"))
    )
    (net (code "92") (name "Net-(DD2-ADKEY2)") (class "Default")
      (node (ref "DD2") (pin "13") (pinfunction "ADKEY2_13") (pintype "passive"))
      (node (ref "SW3") (pin "1") (pinfunction "1_1") (pintype "passive"))
    )
    (net (code "93") (name "Net-(DD2-DAC_L)") (class "Default")
      (node (ref "C16") (pin "1") (pinfunction "1_1") (pintype "passive"))
      (node (ref "DD2") (pin "5") (pinfunction "DAC_L_5") (pintype "passive"))
    )
    (net (code "94") (name "Net-(DD2-DAC_R)") (class "Default")
      (node (ref "C15") (pin "1") (pinfunction "1_1") (pintype "passive"))
      (node (ref "DD2") (pin "4") (pinfunction "DAC_R_4") (pintype "passive"))
    )
    (net (code "95") (name "Net-(DD2-IO1)") (class "Default")
      (node (ref "DD2") (pin "9") (pinfunction "IO1_9") (pintype "passive"))
      (node (ref "SW4") (pin "1") (pinfunction "1_1") (pintype "passive"))
    )
    (net (code "96") (name "Net-(DD2-IO2)") (class "Default")
      (node (ref "DD2") (pin "11") (pinfunction "IO2_11") (pintype "passive"))
      (node (ref "SW5") (pin "1") (pinfunction "1_1") (pintype "passive"))
    )
    (net (code "97") (name "Net-(DD2-RX)") (class "Default")
      (node (ref "DD2") (pin "2") (pinfunction "RX_2") (pintype "passive"))
      (node (ref "R5") (pin "2") (pinfunction "2_2") (pintype "passive"))
    )
    (net (code "98") (name "Net-(DD3-DTR)") (class "Default")
      (node (ref "C10") (pin "2") (pinfunction "2_2") (pintype "passive"))
      (node (ref "DD3") (pin "23") (pinfunction "DTR_23") (pintype "passive"))
    )
    (net (code "99") (name "Net-(DD3-GPIO.0)") (class "Default")
      (node (ref "DD3") (pin "14") (pinfunction "GPIO.0_14") (pintype "passive"))
      (node (ref "VD1") (pin "1") (pinfunction "K_1") (pintype "passive"))
    )
    (net (code "100") (name "Net-(DD3-GPIO.1)") (class "Default")
      (node (ref "DD3") (pin "13") (pinfunction "GPIO.1_13") (pintype "passive"))
      (node (ref "VD2") (pin "1") (pinfunction "K_1") (pintype "passive"))
    )
    (net (code "101") (name "Net-(DD3-RST)") (class "Default")
      (node (ref "DD3") (pin "9") (pinfunction "RST_9") (pintype "passive"))
      (node (ref "R9") (pin "1") (pinfunction "1_1") (pintype "passive"))
    )
    (net (code "102") (name "Net-(DD3-RXD)") (class "Default")
      (node (ref "DD3") (pin "20") (pinfunction "RXD_20") (pintype "passive"))
      (node (ref "R7") (pin "2") (pinfunction "2_2") (pintype "passive"))
    )
    (net (code "103") (name "Net-(DD3-TXD)") (class "Default")
      (node (ref "DD3") (pin "21") (pinfunction "TXD_21") (pintype "passive"))
      (node (ref "R6") (pin "2") (pinfunction "2_2") (pintype "passive"))
    )
    (net (code "104") (name "Net-(DD3-VDD)") (class "Default")
      (node (ref "C17") (pin "2") (pinfunction "2_2") (pintype "passive"))
      (node (ref "C19") (pin "2") (pinfunction "2_2") (pintype "passive"))
      (node (ref "C22") (pin "2") (pinfunction "2_2") (pintype "passive"))
      (node (ref "DD3") (pin "5") (pinfunction "VIO_5") (pintype "passive"))
      (node (ref "DD3") (pin "6") (pinfunction "VDD_6") (pintype "passive"))
      (node (ref "R9") (pin "2") (pinfunction "2_2") (pintype "passive"))
    )
    (net (code "105") (name "Net-(DD3-VPP)") (class "Default")
      (node (ref "C13") (pin "2") (pinfunction "2_2") (pintype "passive"))
      (node (ref "DD3") (pin "16") (pinfunction "VPP_16") (pintype "passive"))
    )
    (net (code "106") (name "Net-(DD4-+IN)") (class "Default")
      (node (ref "C20") (pin "2") (pinfunction "2_2") (pintype "passive"))
      (node (ref "DD4") (pin "1") (pinfunction "+IN_1") (pintype "passive"))
      (node (ref "R19") (pin "2") (pinfunction "2_2") (pintype "passive"))
    )
    (net (code "107") (name "Net-(DD4--IN)") (class "Default")
      (node (ref "C26") (pin "2") (pinfunction "2_2") (pintype "passive"))
      (node (ref "DD4") (pin "2") (pinfunction "-IN_2") (pintype "passive"))
      (node (ref "R26") (pin "1") (pinfunction "1_1") (pintype "passive"))
    )
    (net (code "108") (name "Net-(DD4-OUT)") (class "Default")
      (node (ref "C27") (pin "2") (pinfunction "2_2") (pintype "passive"))
      (node (ref "C28") (pin "1") (pinfunction "1_1") (pintype "passive"))
      (node (ref "DD4") (pin "4") (pinfunction "OUT_4") (pintype "passive"))
      (node (ref "R26") (pin "2") (pinfunction "2_2") (pintype "passive"))
      (node (ref "VD4") (pin "1") (pinfunction "K_1") (pintype "passive"))
      (node (ref "VD5") (pin "2") (pinfunction "A_2") (pintype "passive"))
    )
    (net (code "109") (name "Net-(R21-Pad1)") (class "Default")
      (node (ref "R21") (pin "1") (pinfunction "1_1") (pintype "passive"))
      (node (ref "SW6") (pin "6") (pinfunction "6_6") (pintype "passive"))
    )
    (net (code "110") (name "Net-(R22-Pad1)") (class "Default")
      (node (ref "R22") (pin "1") (pinfunction "1_1") (pintype "passive"))
      (node (ref "SW7") (pin "6") (pinfunction "6_6") (pintype "passive"))
    )
    (net (code "111") (name "Net-(R23-Pad1)") (class "Default")
      (node (ref "R23") (pin "1") (pinfunction "1_1") (pintype "passive"))
      (node (ref "SW8") (pin "6") (pinfunction "6_6") (pintype "passive"))
    )
    (net (code "112") (name "Net-(VD1-A)") (class "Default")
      (node (ref "R10") (pin "1") (pinfunction "1_1") (pintype "passive"))
      (node (ref "VD1") (pin "2") (pinfunction "A_2") (pintype "passive"))
    )
    (net (code "113") (name "Net-(VD2-A)") (class "Default")
      (node (ref "R11") (pin "1") (pinfunction "1_1") (pintype "passive"))
      (node (ref "VD2") (pin "2") (pinfunction "A_2") (pintype "passive"))
    )
    (net (code "114") (name "Net-(VD3-A)") (class "Default")
      (node (ref "VD3") (pin "2") (pinfunction "A_2") (pintype "passive"))
      (node (ref "X3") (pin "9") (pinfunction "GND_9") (pintype "passive"))
    )
    (net (code "115") (name "Net-(X3-A5)") (class "Default")
      (node (ref "R20") (pin "2") (pinfunction "2_2") (pintype "passive"))
      (node (ref "X3") (pin "2") (pinfunction "A5_2") (pintype "passive"))
    )
    (net (code "116") (name "Net-(X3-B5)") (class "Default")
      (node (ref "R18") (pin "2") (pinfunction "2_2") (pintype "passive"))
      (node (ref "X3") (pin "8") (pinfunction "B5_8") (pintype "passive"))
    )
    (net (code "117") (name "unconnected-(DD1-CLKO_{slash}_ICP3_{slash}_INT7_{slash}_PE7-Pad9)") (class "Default")
      (node (ref "DD1") (pin "9") (pinfunction "CLKO_/_ICP3_/_INT7_/_PE7_9") (pintype "passive"))
    )
    (net (code "118") (name "unconnected-(DD1-ICP1_{slash}_PD4-Pad47)") (class "Default")
      (node (ref "DD1") (pin "47") (pinfunction "ICP1_/_PD4_47") (pintype "passive"))
    )
    (net (code "119") (name "unconnected-(DD1-PC5{slash}_A13-Pad58)") (class "Default")
      (node (ref "DD1") (pin "58") (pinfunction "PC5/_A13_58") (pintype "passive"))
    )
    (net (code "120") (name "unconnected-(DD1-PC7_{slash}_A15-Pad60)") (class "Default")
      (node (ref "DD1") (pin "60") (pinfunction "PC7_/_A15_60") (pintype "passive"))
    )
    (net (code "121") (name "unconnected-(DD1-PF7_{slash}_ADC7_{slash}_TDI-Pad90)") (class "Default")
      (node (ref "DD1") (pin "90") (pinfunction "PF7_/_ADC7_/_TDI_90") (pintype "passive"))
    )
    (net (code "122") (name "unconnected-(DD1-PJ2_{slash}_XCK3_{slash}_PCINT11-Pad65)") (class "Default")
      (node (ref "DD1") (pin "65") (pinfunction "PJ2_/_XCK3_/_PCINT11_65") (pintype "passive"))
    )
    (net (code "123") (name "unconnected-(DD1-PJ3_{slash}_PCINT12-Pad66)") (class "Default")
      (node (ref "DD1") (pin "66") (pinfunction "PJ3_/_PCINT12_66") (pintype "passive"))
    )
    (net (code "124") (name "unconnected-(DD1-PJ4_{slash}_PCINT13-Pad67)") (class "Default")
      (node (ref "DD1") (pin "67") (pinfunction "PJ4_/_PCINT13_67") (pintype "passive"))
    )
    (net (code "125") (name "unconnected-(DD1-PJ5_{slash}_PCINT14-Pad68)") (class "Default")
      (node (ref "DD1") (pin "68") (pinfunction "PJ5_/_PCINT14_68") (pintype "passive"))
    )
    (net (code "126") (name "unconnected-(DD1-PJ6_{slash}_PCINT15-Pad69)") (class "Default")
      (node (ref "DD1") (pin "69") (pinfunction "PJ6_/_PCINT15_69") (pintype "passive"))
    )
    (net (code "127") (name "unconnected-(DD1-PJ7-Pad79)") (class "Default")
      (node (ref "DD1") (pin "79") (pinfunction "PJ7_79") (pintype "passive"))
    )
    (net (code "128") (name "unconnected-(DD1-SS_{slash}_PCINT0_{slash}_PB0-Pad19)") (class "Default")
      (node (ref "DD1") (pin "19") (pinfunction "SS_/_PCINT0_/_PB0_19") (pintype "passive"))
    )
    (net (code "129") (name "unconnected-(DD1-T1_{slash}_PD6-Pad49)") (class "Default")
      (node (ref "DD1") (pin "49") (pinfunction "T1_/_PD6_49") (pintype "passive"))
    )
    (net (code "130") (name "unconnected-(DD1-T3_{slash}_INT6_{slash}_PE6-Pad8)") (class "Default")
      (node (ref "DD1") (pin "8") (pinfunction "T3_/_INT6_/_PE6_8") (pintype "passive"))
    )
    (net (code "131") (name "unconnected-(DD1-T4_{slash}_PH7-Pad27)") (class "Default")
      (node (ref "DD1") (pin "27") (pinfunction "T4_/_PH7_27") (pintype "passive"))
    )
    (net (code "132") (name "unconnected-(DD1-TOSC1_{slash}_PG4-Pad29)") (class "Default")
      (node (ref "DD1") (pin "29") (pinfunction "TOSC1_/_PG4_29") (pintype "passive"))
    )
    (net (code "133") (name "unconnected-(DD1-TOSC2_{slash}_PG3-Pad28)") (class "Default")
      (node (ref "DD1") (pin "28") (pinfunction "TOSC2_/_PG3_28") (pintype "passive"))
    )
    (net (code "134") (name "unconnected-(DD1-XCK0_{slash}_AIN0_{slash}_PE2-Pad4)") (class "Default")
      (node (ref "DD1") (pin "4") (pinfunction "XCK0_/_AIN0_/_PE2_4") (pintype "passive"))
    )
    (net (code "135") (name "unconnected-(DD1-XCK1_{slash}_PD5-Pad48)") (class "Default")
      (node (ref "DD1") (pin "48") (pinfunction "XCK1_/_PD5_48") (pintype "passive"))
    )
    (net (code "136") (name "unconnected-(DD1-XCK2_{slash}_PH2-Pad14)") (class "Default")
      (node (ref "DD1") (pin "14") (pinfunction "XCK2_/_PH2_14") (pintype "passive"))
    )
    (net (code "137") (name "unconnected-(DD2-BUSY-Pad16)") (class "Default")
      (node (ref "DD2") (pin "16") (pinfunction "BUSY_16") (pintype "passive"))
    )
    (net (code "138") (name "unconnected-(DD2-SPK1-Pad8)") (class "Default")
      (node (ref "DD2") (pin "8") (pinfunction "SPK1_8") (pintype "passive"))
    )
    (net (code "139") (name "unconnected-(DD2-SPK2-Pad6)") (class "Default")
      (node (ref "DD2") (pin "6") (pinfunction "SPK2_6") (pintype "passive"))
    )
    (net (code "140") (name "unconnected-(DD2-USB+-Pad14)") (class "Default")
      (node (ref "DD2") (pin "14") (pinfunction "USB+_14") (pintype "passive"))
    )
    (net (code "141") (name "unconnected-(DD2-USB--Pad15)") (class "Default")
      (node (ref "DD2") (pin "15") (pinfunction "USB-_15") (pintype "passive"))
    )
    (net (code "142") (name "unconnected-(DD3-CTS-Pad18)") (class "Default")
      (node (ref "DD3") (pin "18") (pinfunction "CTS_18") (pintype "passive"))
    )
    (net (code "143") (name "unconnected-(DD3-DCD-Pad24)") (class "Default")
      (node (ref "DD3") (pin "24") (pinfunction "DCD_24") (pintype "passive"))
    )
    (net (code "144") (name "unconnected-(DD3-DSR-Pad22)") (class "Default")
      (node (ref "DD3") (pin "22") (pinfunction "DSR_22") (pintype "passive"))
    )
    (net (code "145") (name "unconnected-(DD3-GPIO.2-Pad12)") (class "Default")
      (node (ref "DD3") (pin "12") (pinfunction "GPIO.2_12") (pintype "passive"))
    )
    (net (code "146") (name "unconnected-(DD3-GPIO.3-Pad11)") (class "Default")
      (node (ref "DD3") (pin "11") (pinfunction "GPIO.3_11") (pintype "passive"))
    )
    (net (code "147") (name "unconnected-(DD3-NC-Pad10)") (class "Default")
      (node (ref "DD3") (pin "10") (pinfunction "NC_10") (pintype "passive"))
    )
    (net (code "148") (name "unconnected-(DD3-RI-Pad1)") (class "Default")
      (node (ref "DD3") (pin "1") (pinfunction "RI_1") (pintype "passive"))
    )
    (net (code "149") (name "unconnected-(DD3-RTS-Pad19)") (class "Default")
      (node (ref "DD3") (pin "19") (pinfunction "RTS_19") (pintype "passive"))
    )
    (net (code "150") (name "unconnected-(DD3-SUSPEND-Pad17)") (class "Default")
      (node (ref "DD3") (pin "17") (pinfunction "SUSPEND_17") (pintype "passive"))
    )
    (net (code "151") (name "unconnected-(DD3-~{SUSPEND}-Pad15)") (class "Default")
      (node (ref "DD3") (pin "15") (pinfunction "~{SUSPEND}_15") (pintype "passive"))
    )
    (net (code "152") (name "unconnected-(R8-Pad1)") (class "Default")
      (node (ref "R8") (pin "1") (pinfunction "1_1") (pintype "passive"))
    )
    (net (code "153") (name "unconnected-(R8-Pad2)") (class "Default")
      (node (ref "R8") (pin "2") (pinfunction "2_2") (pintype "passive"))
    )
    (net (code "154") (name "unconnected-(X3-A8-Pad7)") (class "Default")
      (node (ref "X3") (pin "7") (pinfunction "A8_7") (pintype "passive"))
    )
    (net (code "155") (name "unconnected-(X3-B8-Pad1)") (class "Default")
      (node (ref "X3") (pin "1") (pinfunction "B8_1") (pintype "passive"))
    )
  )
)
